# motorboard_2017.net
KiCad netlist of a schematic drawn in EAGLE
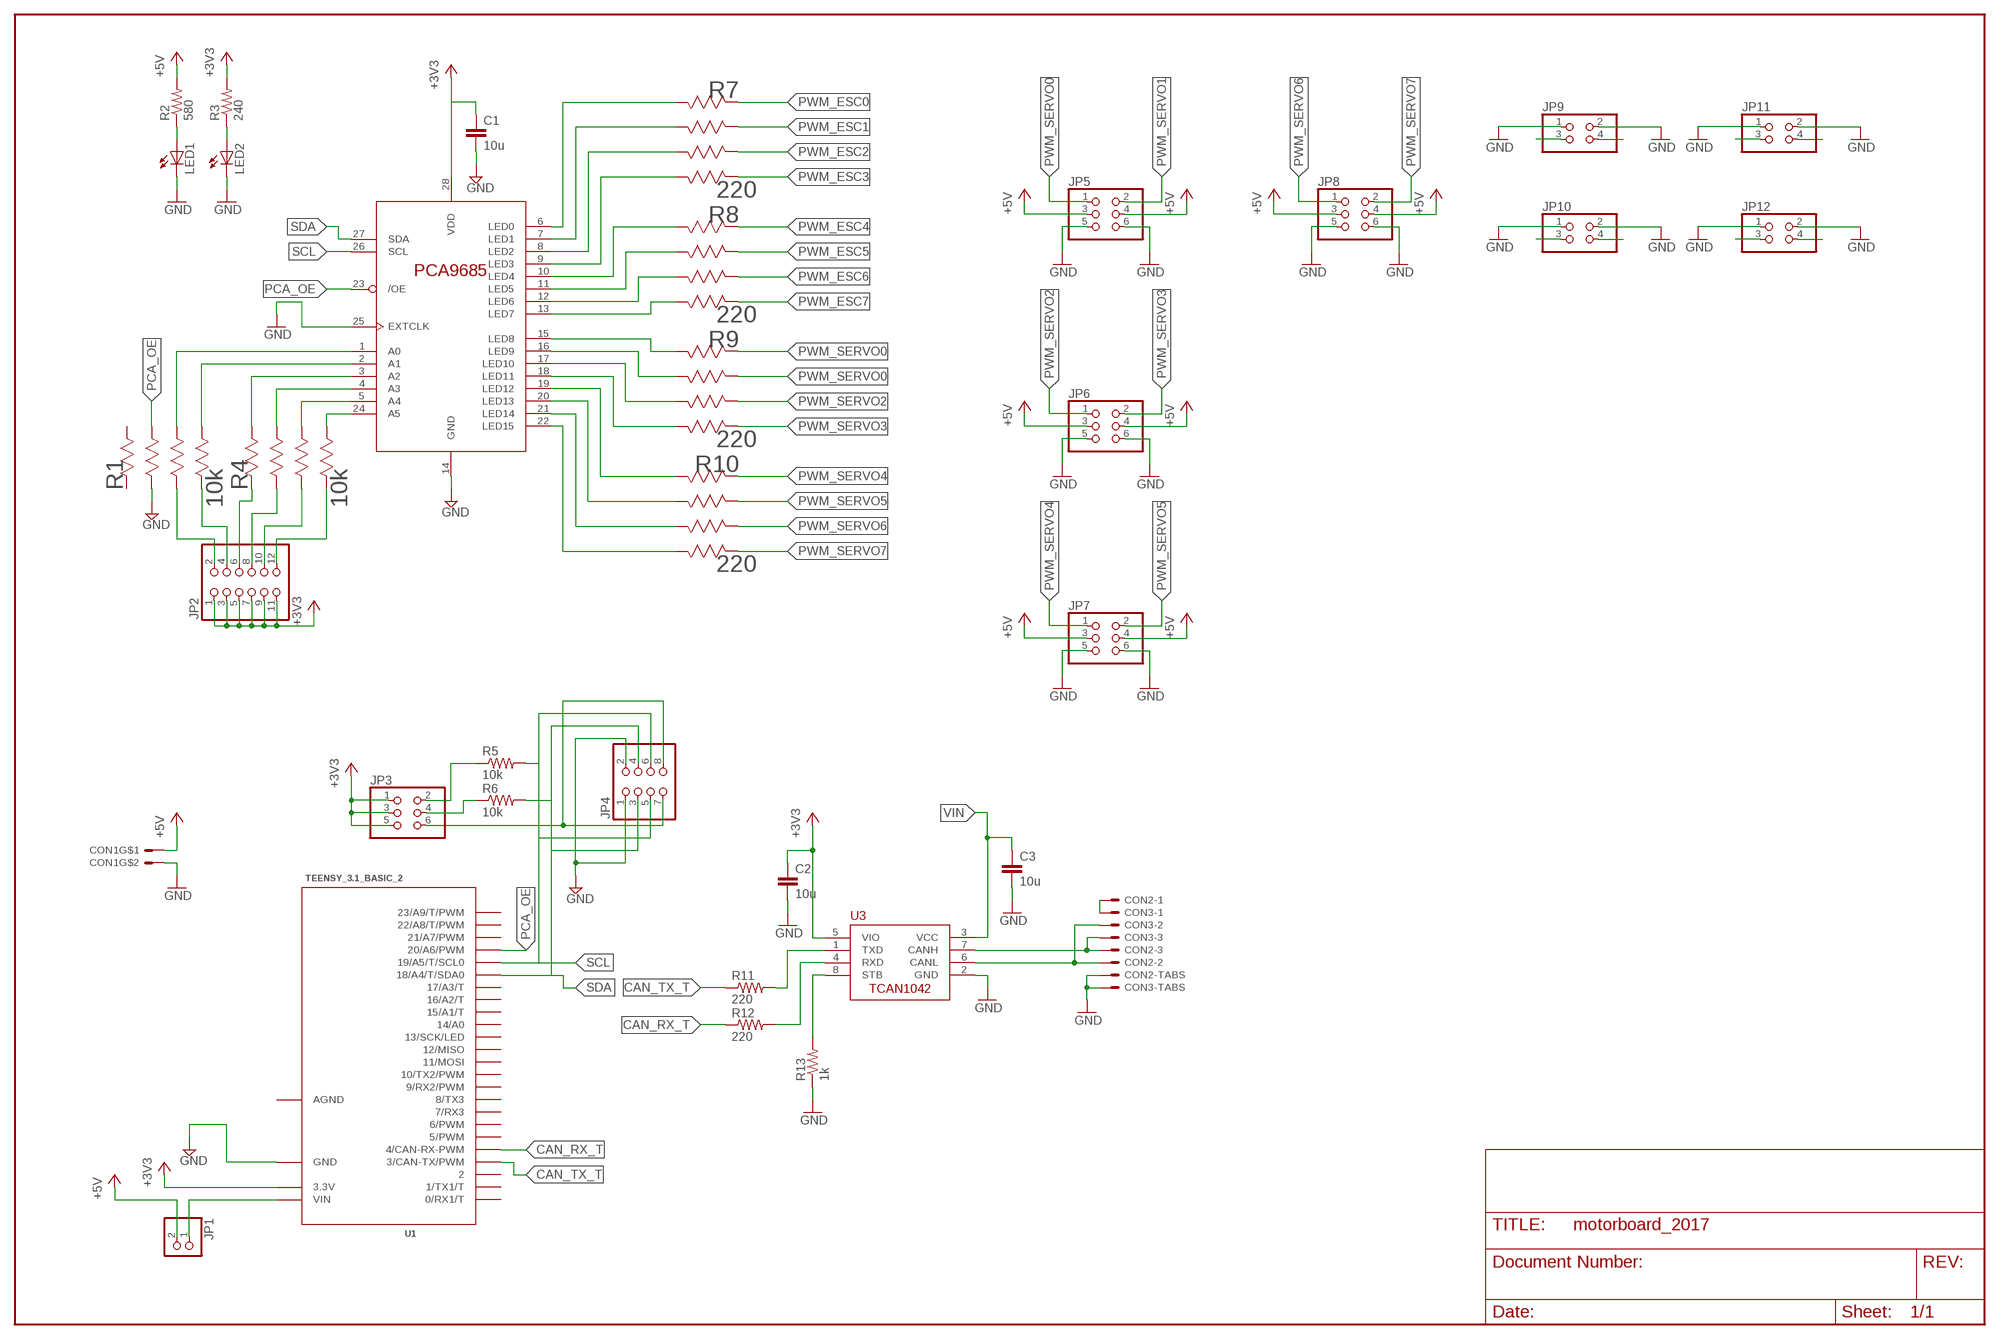
[diagram p0: schematic, sheet 1]

(export (version "E")
  (design (tool "Eeschema 10.0.6"))
  (components
    (comp (ref "C1")
      (value "10u")
      (footprint "eagle-import:C0805")
      (libsource (lib "eagle-import") (part "C-EUC0805"))
    )
    (comp (ref "C2")
      (value "10u")
      (footprint "eagle-import:C0805")
      (libsource (lib "eagle-import") (part "C-EUC0805"))
    )
    (comp (ref "C3")
      (value "10u")
      (footprint "eagle-import:C0805")
      (libsource (lib "eagle-import") (part "C-EUC0805"))
    )
    (comp (ref "CON1")
      (value "MOLEX_5566-2")
      (footprint "eagle-import:5566-2")
      (libsource (lib "eagle-import") (part "MOLEX_5566-2"))
    )
    (comp (ref "CON2")
      (value "SM03B-GHS-TB")
      (footprint "eagle-import:SM03B-GHS-TB")
      (libsource (lib "eagle-import") (part "SM03B-GHS-TB"))
    )
    (comp (ref "CON3")
      (value "SM03B-GHS-TB")
      (footprint "eagle-import:SM03B-GHS-TB")
      (libsource (lib "eagle-import") (part "SM03B-GHS-TB"))
    )
    (comp (ref "JP1")
      (value "PINHD-1X2")
      (footprint "eagle-import:1X02")
      (libsource (lib "eagle-import") (part "PINHD-1X2"))
    )
    (comp (ref "JP2")
      (value "PINHD-2X6")
      (footprint "eagle-import:2X06")
      (libsource (lib "eagle-import") (part "PINHD-2X6"))
    )
    (comp (ref "JP3")
      (value "PINHD-2X3")
      (footprint "eagle-import:2X03")
      (libsource (lib "eagle-import") (part "PINHD-2X3"))
    )
    (comp (ref "JP4")
      (value "PINHD-2X4")
      (footprint "eagle-import:2X04")
      (libsource (lib "eagle-import") (part "PINHD-2X4"))
    )
    (comp (ref "JP5")
      (value "PINHD-2X3")
      (footprint "eagle-import:2X03")
      (libsource (lib "eagle-import") (part "PINHD-2X3"))
    )
    (comp (ref "JP6")
      (value "PINHD-2X3")
      (footprint "eagle-import:2X03")
      (libsource (lib "eagle-import") (part "PINHD-2X3"))
    )
    (comp (ref "JP7")
      (value "PINHD-2X3")
      (footprint "eagle-import:2X03")
      (libsource (lib "eagle-import") (part "PINHD-2X3"))
    )
    (comp (ref "JP8")
      (value "PINHD-2X3")
      (footprint "eagle-import:2X03")
      (libsource (lib "eagle-import") (part "PINHD-2X3"))
    )
    (comp (ref "JP9")
      (value "PINHD-2X2")
      (footprint "eagle-import:2X02")
      (libsource (lib "eagle-import") (part "PINHD-2X2"))
    )
    (comp (ref "JP10")
      (value "PINHD-2X2")
      (footprint "eagle-import:2X02")
      (libsource (lib "eagle-import") (part "PINHD-2X2"))
    )
    (comp (ref "JP11")
      (value "PINHD-2X2")
      (footprint "eagle-import:2X02")
      (libsource (lib "eagle-import") (part "PINHD-2X2"))
    )
    (comp (ref "JP12")
      (value "PINHD-2X2")
      (footprint "eagle-import:2X02")
      (libsource (lib "eagle-import") (part "PINHD-2X2"))
    )
    (comp (ref "LED1")
      (value "LEDCHIPLED_1206")
      (footprint "eagle-import:CHIPLED_1206")
      (libsource (lib "eagle-import") (part "LEDCHIPLED_1206"))
    )
    (comp (ref "LED2")
      (value "LEDCHIPLED_1206")
      (footprint "eagle-import:CHIPLED_1206")
      (libsource (lib "eagle-import") (part "LEDCHIPLED_1206"))
    )
    (comp (ref "R1")
      (value "10k")
      (footprint "eagle-import:EXBV8V-M")
      (fields (field (name "MANUFACTURER_PART_NUMBER") "EXBV8V221JV"))
      (libsource (lib "eagle-import") (part "EXB-V8V221JVEXBV8V-M"))
    )
    (comp (ref "R2")
      (value "580")
      (footprint "eagle-import:R1206")
      (libsource (lib "eagle-import") (part "R-US_R1206"))
    )
    (comp (ref "R3")
      (value "240")
      (footprint "eagle-import:R1206")
      (libsource (lib "eagle-import") (part "R-US_R1206"))
    )
    (comp (ref "R4")
      (value "10k")
      (footprint "eagle-import:EXBV8V-M")
      (fields (field (name "MANUFACTURER_PART_NUMBER") "EXBV8V221JV"))
      (libsource (lib "eagle-import") (part "EXB-V8V221JVEXBV8V-M"))
    )
    (comp (ref "R5")
      (value "10k")
      (footprint "eagle-import:R1206")
      (libsource (lib "eagle-import") (part "R-US_R1206"))
    )
    (comp (ref "R6")
      (value "10k")
      (footprint "eagle-import:R1206")
      (libsource (lib "eagle-import") (part "R-US_R1206"))
    )
    (comp (ref "R7")
      (value "220")
      (footprint "eagle-import:EXBV8V-M")
      (fields (field (name "MANUFACTURER_PART_NUMBER") "EXBV8V221JV"))
      (libsource (lib "eagle-import") (part "EXB-V8V221JVEXBV8V-M"))
    )
    (comp (ref "R8")
      (value "220")
      (footprint "eagle-import:EXBV8V-M")
      (fields (field (name "MANUFACTURER_PART_NUMBER") "EXBV8V221JV"))
      (libsource (lib "eagle-import") (part "EXB-V8V221JVEXBV8V-M"))
    )
    (comp (ref "R9")
      (value "220")
      (footprint "eagle-import:EXBV8V-M")
      (fields (field (name "MANUFACTURER_PART_NUMBER") "EXBV8V221JV"))
      (libsource (lib "eagle-import") (part "EXB-V8V221JVEXBV8V-M"))
    )
    (comp (ref "R10")
      (value "220")
      (footprint "eagle-import:EXBV8V-M")
      (fields (field (name "MANUFACTURER_PART_NUMBER") "EXBV8V221JV"))
      (libsource (lib "eagle-import") (part "EXB-V8V221JVEXBV8V-M"))
    )
    (comp (ref "R11")
      (value "220")
      (footprint "eagle-import:R0805")
      (libsource (lib "eagle-import") (part "R-US_R0805"))
    )
    (comp (ref "R12")
      (value "220")
      (footprint "eagle-import:R0805")
      (libsource (lib "eagle-import") (part "R-US_R0805"))
    )
    (comp (ref "R13")
      (value "1k")
      (footprint "eagle-import:R0805")
      (libsource (lib "eagle-import") (part "R-US_R0805"))
    )
    (comp (ref "U1")
      (value "TEENSY_3.1_BASIC_2")
      (footprint "eagle-import:TEENSY_3.1_BASIC_2")
      (libsource (lib "eagle-import") (part "TEENSY_3.1_BASIC_2"))
    )
    (comp (ref "U2")
      (value "PCA9685PW")
      (footprint "eagle-import:TSSOP28")
      (libsource (lib "eagle-import") (part "PCA9685PW"))
    )
    (comp (ref "U3")
      (value "TCAN1042HVDR")
      (footprint "eagle-import:SO-8")
      (libsource (lib "eagle-import") (part "TCAN1042HVDR"))
    )
  )
  (nets
    (net (code "1") (name "+3V3") (class "Default")
      (node (ref "C1") (pin "1") (pinfunction "1_1") (pintype "passive"))
      (node (ref "C2") (pin "1") (pinfunction "1_1") (pintype "passive"))
      (node (ref "JP2") (pin "1") (pinfunction "1_1") (pintype "passive"))
      (node (ref "JP2") (pin "11") (pinfunction "11_11") (pintype "passive"))
      (node (ref "JP2") (pin "3") (pinfunction "3_3") (pintype "passive"))
      (node (ref "JP2") (pin "5") (pinfunction "5_5") (pintype "passive"))
      (node (ref "JP2") (pin "7") (pinfunction "7_7") (pintype "passive"))
      (node (ref "JP2") (pin "9") (pinfunction "9_9") (pintype "passive"))
      (node (ref "JP3") (pin "1") (pinfunction "1_1") (pintype "passive"))
      (node (ref "JP3") (pin "3") (pinfunction "3_3") (pintype "passive"))
      (node (ref "JP3") (pin "5") (pinfunction "5_5") (pintype "passive"))
      (node (ref "R3") (pin "2") (pinfunction "2_2") (pintype "passive"))
      (node (ref "U1") (pin "3.3V") (pinfunction "3.3V_3.3V") (pintype "power_in"))
      (node (ref "U2") (pin "28") (pinfunction "VDD_28") (pintype "power_in"))
      (node (ref "U3") (pin "5") (pinfunction "VIO_5") (pintype "bidirectional"))
    )
    (net (code "2") (name "+5V") (class "Default")
      (node (ref "CON1") (pin "1") (pinfunction "S_1") (pintype "passive"))
      (node (ref "JP1") (pin "2") (pinfunction "2_2") (pintype "passive"))
      (node (ref "JP5") (pin "3") (pinfunction "3_3") (pintype "passive"))
      (node (ref "JP5") (pin "4") (pinfunction "4_4") (pintype "passive"))
      (node (ref "JP6") (pin "3") (pinfunction "3_3") (pintype "passive"))
      (node (ref "JP6") (pin "4") (pinfunction "4_4") (pintype "passive"))
      (node (ref "JP7") (pin "3") (pinfunction "3_3") (pintype "passive"))
      (node (ref "JP7") (pin "4") (pinfunction "4_4") (pintype "passive"))
      (node (ref "JP8") (pin "3") (pinfunction "3_3") (pintype "passive"))
      (node (ref "JP8") (pin "4") (pinfunction "4_4") (pintype "passive"))
      (node (ref "R2") (pin "2") (pinfunction "2_2") (pintype "passive"))
    )
    (net (code "3") (name "/AGND") (class "Default")
      (node (ref "U1") (pin "AGND") (pinfunction "AGND_AGND") (pintype "power_in"))
    )
    (net (code "4") (name "CAN_RX_T") (class "Default")
      (node (ref "R12") (pin "1") (pinfunction "1_1") (pintype "passive"))
      (node (ref "U1") (pin "4") (pinfunction "4/CAN-RX-PWM_4") (pintype "bidirectional"))
    )
    (net (code "5") (name "CAN_TX_T") (class "Default")
      (node (ref "R11") (pin "1") (pinfunction "1_1") (pintype "passive"))
      (node (ref "U1") (pin "3") (pinfunction "3/CAN-TX/PWM_3") (pintype "bidirectional"))
    )
    (net (code "6") (name "GND") (class "Default")
      (node (ref "C1") (pin "2") (pinfunction "2_2") (pintype "passive"))
      (node (ref "C2") (pin "2") (pinfunction "2_2") (pintype "passive"))
      (node (ref "C3") (pin "2") (pinfunction "2_2") (pintype "passive"))
      (node (ref "CON1") (pin "2") (pinfunction "S_2") (pintype "passive"))
      (node (ref "CON2") (pin "P$4") (pinfunction "S_P$4") (pintype "passive"))
      (node (ref "CON2") (pin "P$5") (pinfunction "S_P$5") (pintype "passive"))
      (node (ref "CON3") (pin "P$4") (pinfunction "S_P$4") (pintype "passive"))
      (node (ref "CON3") (pin "P$5") (pinfunction "S_P$5") (pintype "passive"))
      (node (ref "JP10") (pin "1") (pinfunction "1_1") (pintype "passive"))
      (node (ref "JP10") (pin "2") (pinfunction "2_2") (pintype "passive"))
      (node (ref "JP11") (pin "1") (pinfunction "1_1") (pintype "passive"))
      (node (ref "JP11") (pin "2") (pinfunction "2_2") (pintype "passive"))
      (node (ref "JP12") (pin "1") (pinfunction "1_1") (pintype "passive"))
      (node (ref "JP12") (pin "2") (pinfunction "2_2") (pintype "passive"))
      (node (ref "JP4") (pin "1") (pinfunction "1_1") (pintype "passive"))
      (node (ref "JP4") (pin "2") (pinfunction "2_2") (pintype "passive"))
      (node (ref "JP5") (pin "5") (pinfunction "5_5") (pintype "passive"))
      (node (ref "JP5") (pin "6") (pinfunction "6_6") (pintype "passive"))
      (node (ref "JP6") (pin "5") (pinfunction "5_5") (pintype "passive"))
      (node (ref "JP6") (pin "6") (pinfunction "6_6") (pintype "passive"))
      (node (ref "JP7") (pin "5") (pinfunction "5_5") (pintype "passive"))
      (node (ref "JP7") (pin "6") (pinfunction "6_6") (pintype "passive"))
      (node (ref "JP8") (pin "5") (pinfunction "5_5") (pintype "passive"))
      (node (ref "JP8") (pin "6") (pinfunction "6_6") (pintype "passive"))
      (node (ref "JP9") (pin "1") (pinfunction "1_1") (pintype "passive"))
      (node (ref "JP9") (pin "2") (pinfunction "2_2") (pintype "passive"))
      (node (ref "LED1") (pin "C") (pinfunction "C_C") (pintype "passive"))
      (node (ref "LED2") (pin "C") (pinfunction "C_C") (pintype "passive"))
      (node (ref "R1") (pin "2") (pinfunction "23_2") (pintype "passive"))
      (node (ref "R13") (pin "1") (pinfunction "1_1") (pintype "passive"))
      (node (ref "U1") (pin "GND") (pinfunction "GND_GND") (pintype "power_in"))
      (node (ref "U2") (pin "14") (pinfunction "GND_14") (pintype "power_in"))
      (node (ref "U2") (pin "25") (pinfunction "EXTCLK_25") (pintype "input"))
      (node (ref "U3") (pin "2") (pinfunction "GND_2") (pintype "bidirectional"))
    )
    (net (code "7") (name "Net-(CON2A-S)") (class "Default")
      (node (ref "CON2") (pin "P$1") (pinfunction "S_P$1") (pintype "passive"))
      (node (ref "CON3") (pin "P$1") (pinfunction "S_P$1") (pintype "passive"))
    )
    (net (code "8") (name "Net-(CON2B-S)") (class "Default")
      (node (ref "CON2") (pin "P$2") (pinfunction "S_P$2") (pintype "passive"))
      (node (ref "CON3") (pin "P$2") (pinfunction "S_P$2") (pintype "passive"))
      (node (ref "U3") (pin "6") (pinfunction "CANL_6") (pintype "bidirectional"))
    )
    (net (code "9") (name "Net-(CON2C-S)") (class "Default")
      (node (ref "CON2") (pin "P$3") (pinfunction "S_P$3") (pintype "passive"))
      (node (ref "CON3") (pin "P$3") (pinfunction "S_P$3") (pintype "passive"))
      (node (ref "U3") (pin "7") (pinfunction "CANH_7") (pintype "bidirectional"))
    )
    (net (code "10") (name "Net-(JP3-Pad2)") (class "Default")
      (node (ref "JP3") (pin "2") (pinfunction "2_2") (pintype "passive"))
      (node (ref "R5") (pin "1") (pinfunction "1_1") (pintype "passive"))
    )
    (net (code "11") (name "Net-(JP3-Pad4)") (class "Default")
      (node (ref "JP3") (pin "4") (pinfunction "4_4") (pintype "passive"))
      (node (ref "R6") (pin "1") (pinfunction "1_1") (pintype "passive"))
    )
    (net (code "12") (name "Net-(JP3-Pad6)") (class "Default")
      (node (ref "JP3") (pin "6") (pinfunction "6_6") (pintype "passive"))
      (node (ref "JP4") (pin "7") (pinfunction "7_7") (pintype "passive"))
      (node (ref "JP4") (pin "8") (pinfunction "8_8") (pintype "passive"))
    )
    (net (code "13") (name "Net-(LED1-PadA)") (class "Default")
      (node (ref "LED1") (pin "A") (pinfunction "A_A") (pintype "passive"))
      (node (ref "R2") (pin "1") (pinfunction "1_1") (pintype "passive"))
    )
    (net (code "14") (name "Net-(LED2-PadA)") (class "Default")
      (node (ref "LED2") (pin "A") (pinfunction "A_A") (pintype "passive"))
      (node (ref "R3") (pin "1") (pinfunction "1_1") (pintype "passive"))
    )
    (net (code "15") (name "Net-(R1-35)") (class "Default")
      (node (ref "JP2") (pin "2") (pinfunction "2_2") (pintype "passive"))
      (node (ref "R1") (pin "3") (pinfunction "35_3") (pintype "passive"))
    )
    (net (code "16") (name "Net-(R1-47)") (class "Default")
      (node (ref "JP2") (pin "4") (pinfunction "4_4") (pintype "passive"))
      (node (ref "R1") (pin "4") (pinfunction "47_4") (pintype "passive"))
    )
    (net (code "17") (name "Net-(R1-58)") (class "Default")
      (node (ref "R1") (pin "5") (pinfunction "58_5") (pintype "passive"))
      (node (ref "U2") (pin "2") (pinfunction "A1_2") (pintype "bidirectional"))
    )
    (net (code "18") (name "Net-(R1-66)") (class "Default")
      (node (ref "R1") (pin "6") (pinfunction "66_6") (pintype "passive"))
      (node (ref "U2") (pin "1") (pinfunction "A0_1") (pintype "bidirectional"))
    )
    (net (code "19") (name "Net-(R4-11)") (class "Default")
      (node (ref "JP2") (pin "6") (pinfunction "6_6") (pintype "passive"))
      (node (ref "R4") (pin "1") (pinfunction "11_1") (pintype "passive"))
    )
    (net (code "20") (name "Net-(R4-23)") (class "Default")
      (node (ref "JP2") (pin "8") (pinfunction "8_8") (pintype "passive"))
      (node (ref "R4") (pin "2") (pinfunction "23_2") (pintype "passive"))
    )
    (net (code "21") (name "Net-(R4-35)") (class "Default")
      (node (ref "JP2") (pin "10") (pinfunction "10_10") (pintype "passive"))
      (node (ref "R4") (pin "3") (pinfunction "35_3") (pintype "passive"))
    )
    (net (code "22") (name "Net-(R4-47)") (class "Default")
      (node (ref "JP2") (pin "12") (pinfunction "12_12") (pintype "passive"))
      (node (ref "R4") (pin "4") (pinfunction "47_4") (pintype "passive"))
    )
    (net (code "23") (name "Net-(R4-58)") (class "Default")
      (node (ref "R4") (pin "5") (pinfunction "58_5") (pintype "passive"))
      (node (ref "U2") (pin "24") (pinfunction "A5_24") (pintype "bidirectional"))
    )
    (net (code "24") (name "Net-(R4-66)") (class "Default")
      (node (ref "R4") (pin "6") (pinfunction "66_6") (pintype "passive"))
      (node (ref "U2") (pin "5") (pinfunction "A4_5") (pintype "bidirectional"))
    )
    (net (code "25") (name "Net-(R4-74)") (class "Default")
      (node (ref "R4") (pin "7") (pinfunction "74_7") (pintype "passive"))
      (node (ref "U2") (pin "4") (pinfunction "A3_4") (pintype "bidirectional"))
    )
    (net (code "26") (name "Net-(R4-82)") (class "Default")
      (node (ref "R4") (pin "8") (pinfunction "82_8") (pintype "passive"))
      (node (ref "U2") (pin "3") (pinfunction "A2_3") (pintype "bidirectional"))
    )
    (net (code "27") (name "Net-(R7-58)") (class "Default")
      (node (ref "R7") (pin "5") (pinfunction "58_5") (pintype "passive"))
      (node (ref "U2") (pin "9") (pinfunction "LED3_9") (pintype "bidirectional"))
    )
    (net (code "28") (name "Net-(R7-66)") (class "Default")
      (node (ref "R7") (pin "6") (pinfunction "66_6") (pintype "passive"))
      (node (ref "U2") (pin "8") (pinfunction "LED2_8") (pintype "bidirectional"))
    )
    (net (code "29") (name "Net-(R7-74)") (class "Default")
      (node (ref "R7") (pin "7") (pinfunction "74_7") (pintype "passive"))
      (node (ref "U2") (pin "7") (pinfunction "LED1_7") (pintype "bidirectional"))
    )
    (net (code "30") (name "Net-(R7-82)") (class "Default")
      (node (ref "R7") (pin "8") (pinfunction "82_8") (pintype "passive"))
      (node (ref "U2") (pin "6") (pinfunction "LED0_6") (pintype "bidirectional"))
    )
    (net (code "31") (name "Net-(R8-58)") (class "Default")
      (node (ref "R8") (pin "5") (pinfunction "58_5") (pintype "passive"))
      (node (ref "U2") (pin "13") (pinfunction "LED7_13") (pintype "bidirectional"))
    )
    (net (code "32") (name "Net-(R8-66)") (class "Default")
      (node (ref "R8") (pin "6") (pinfunction "66_6") (pintype "passive"))
      (node (ref "U2") (pin "12") (pinfunction "LED6_12") (pintype "bidirectional"))
    )
    (net (code "33") (name "Net-(R8-74)") (class "Default")
      (node (ref "R8") (pin "7") (pinfunction "74_7") (pintype "passive"))
      (node (ref "U2") (pin "11") (pinfunction "LED5_11") (pintype "bidirectional"))
    )
    (net (code "34") (name "Net-(R8-82)") (class "Default")
      (node (ref "R8") (pin "8") (pinfunction "82_8") (pintype "passive"))
      (node (ref "U2") (pin "10") (pinfunction "LED4_10") (pintype "bidirectional"))
    )
    (net (code "35") (name "Net-(R9-58)") (class "Default")
      (node (ref "R9") (pin "5") (pinfunction "58_5") (pintype "passive"))
      (node (ref "U2") (pin "18") (pinfunction "LED11_18") (pintype "bidirectional"))
    )
    (net (code "36") (name "Net-(R9-66)") (class "Default")
      (node (ref "R9") (pin "6") (pinfunction "66_6") (pintype "passive"))
      (node (ref "U2") (pin "17") (pinfunction "LED10_17") (pintype "bidirectional"))
    )
    (net (code "37") (name "Net-(R9-74)") (class "Default")
      (node (ref "R9") (pin "7") (pinfunction "74_7") (pintype "passive"))
      (node (ref "U2") (pin "16") (pinfunction "LED9_16") (pintype "bidirectional"))
    )
    (net (code "38") (name "Net-(R9-82)") (class "Default")
      (node (ref "R9") (pin "8") (pinfunction "82_8") (pintype "passive"))
      (node (ref "U2") (pin "15") (pinfunction "LED8_15") (pintype "bidirectional"))
    )
    (net (code "39") (name "Net-(R10-58)") (class "Default")
      (node (ref "R10") (pin "5") (pinfunction "58_5") (pintype "passive"))
      (node (ref "U2") (pin "22") (pinfunction "LED15_22") (pintype "bidirectional"))
    )
    (net (code "40") (name "Net-(R10-66)") (class "Default")
      (node (ref "R10") (pin "6") (pinfunction "66_6") (pintype "passive"))
      (node (ref "U2") (pin "21") (pinfunction "LED14_21") (pintype "bidirectional"))
    )
    (net (code "41") (name "Net-(R10-74)") (class "Default")
      (node (ref "R10") (pin "7") (pinfunction "74_7") (pintype "passive"))
      (node (ref "U2") (pin "20") (pinfunction "LED13_20") (pintype "bidirectional"))
    )
    (net (code "42") (name "Net-(R10-82)") (class "Default")
      (node (ref "R10") (pin "8") (pinfunction "82_8") (pintype "passive"))
      (node (ref "U2") (pin "19") (pinfunction "LED12_19") (pintype "bidirectional"))
    )
    (net (code "43") (name "Net-(U3-RXD)") (class "Default")
      (node (ref "R12") (pin "2") (pinfunction "2_2") (pintype "passive"))
      (node (ref "U3") (pin "4") (pinfunction "RXD_4") (pintype "bidirectional"))
    )
    (net (code "44") (name "Net-(U3-STB)") (class "Default")
      (node (ref "R13") (pin "2") (pinfunction "2_2") (pintype "passive"))
      (node (ref "U3") (pin "8") (pinfunction "STB_8") (pintype "bidirectional"))
    )
    (net (code "45") (name "Net-(U3-TXD)") (class "Default")
      (node (ref "R11") (pin "2") (pinfunction "2_2") (pintype "passive"))
      (node (ref "U3") (pin "1") (pinfunction "TXD_1") (pintype "bidirectional"))
    )
    (net (code "46") (name "PCA_OE") (class "Default")
      (node (ref "R1") (pin "7") (pinfunction "74_7") (pintype "passive"))
      (node (ref "U1") (pin "20/A6") (pinfunction "20/A6/PWM_20/A6") (pintype "bidirectional"))
      (node (ref "U2") (pin "23") (pinfunction "/OE_23") (pintype "bidirectional"))
    )
    (net (code "47") (name "PWM_ESC0") (class "Default")
      (node (ref "JP12") (pin "4") (pinfunction "4_4") (pintype "passive"))
      (node (ref "R7") (pin "1") (pinfunction "11_1") (pintype "passive"))
    )
    (net (code "48") (name "PWM_ESC1") (class "Default")
      (node (ref "JP12") (pin "3") (pinfunction "3_3") (pintype "passive"))
      (node (ref "R7") (pin "2") (pinfunction "23_2") (pintype "passive"))
    )
    (net (code "49") (name "PWM_ESC2") (class "Default")
      (node (ref "JP9") (pin "4") (pinfunction "4_4") (pintype "passive"))
      (node (ref "R7") (pin "3") (pinfunction "35_3") (pintype "passive"))
    )
    (net (code "50") (name "PWM_ESC3") (class "Default")
      (node (ref "JP9") (pin "3") (pinfunction "3_3") (pintype "passive"))
      (node (ref "R7") (pin "4") (pinfunction "47_4") (pintype "passive"))
    )
    (net (code "51") (name "PWM_ESC4") (class "Default")
      (node (ref "JP11") (pin "4") (pinfunction "4_4") (pintype "passive"))
      (node (ref "R8") (pin "1") (pinfunction "11_1") (pintype "passive"))
    )
    (net (code "52") (name "PWM_ESC5") (class "Default")
      (node (ref "JP11") (pin "3") (pinfunction "3_3") (pintype "passive"))
      (node (ref "R8") (pin "2") (pinfunction "23_2") (pintype "passive"))
    )
    (net (code "53") (name "PWM_ESC6") (class "Default")
      (node (ref "JP10") (pin "4") (pinfunction "4_4") (pintype "passive"))
      (node (ref "R8") (pin "3") (pinfunction "35_3") (pintype "passive"))
    )
    (net (code "54") (name "PWM_ESC7") (class "Default")
      (node (ref "JP10") (pin "3") (pinfunction "3_3") (pintype "passive"))
      (node (ref "R8") (pin "4") (pinfunction "47_4") (pintype "passive"))
    )
    (net (code "55") (name "PWM_SERVO0") (class "Default")
      (node (ref "JP5") (pin "1") (pinfunction "1_1") (pintype "passive"))
      (node (ref "R9") (pin "1") (pinfunction "11_1") (pintype "passive"))
    )
    (net (code "56") (name "PWM_SERVO1") (class "Default")
      (node (ref "JP5") (pin "2") (pinfunction "2_2") (pintype "passive"))
      (node (ref "R9") (pin "2") (pinfunction "23_2") (pintype "passive"))
    )
    (net (code "57") (name "PWM_SERVO2") (class "Default")
      (node (ref "JP6") (pin "1") (pinfunction "1_1") (pintype "passive"))
      (node (ref "R9") (pin "3") (pinfunction "35_3") (pintype "passive"))
    )
    (net (code "58") (name "PWM_SERVO3") (class "Default")
      (node (ref "JP6") (pin "2") (pinfunction "2_2") (pintype "passive"))
      (node (ref "R9") (pin "4") (pinfunction "47_4") (pintype "passive"))
    )
    (net (code "59") (name "PWM_SERVO4") (class "Default")
      (node (ref "JP7") (pin "1") (pinfunction "1_1") (pintype "passive"))
      (node (ref "R10") (pin "1") (pinfunction "11_1") (pintype "passive"))
    )
    (net (code "60") (name "PWM_SERVO5") (class "Default")
      (node (ref "JP7") (pin "2") (pinfunction "2_2") (pintype "passive"))
      (node (ref "R10") (pin "2") (pinfunction "23_2") (pintype "passive"))
    )
    (net (code "61") (name "PWM_SERVO6") (class "Default")
      (node (ref "JP8") (pin "1") (pinfunction "1_1") (pintype "passive"))
      (node (ref "R10") (pin "3") (pinfunction "35_3") (pintype "passive"))
    )
    (net (code "62") (name "PWM_SERVO7") (class "Default")
      (node (ref "JP8") (pin "2") (pinfunction "2_2") (pintype "passive"))
      (node (ref "R10") (pin "4") (pinfunction "47_4") (pintype "passive"))
    )
    (net (code "63") (name "SCL") (class "Default")
      (node (ref "JP4") (pin "5") (pinfunction "5_5") (pintype "passive"))
      (node (ref "JP4") (pin "6") (pinfunction "6_6") (pintype "passive"))
      (node (ref "R5") (pin "2") (pinfunction "2_2") (pintype "passive"))
      (node (ref "U1") (pin "19/A5") (pinfunction "19/A5/T/SCL0_19/A5") (pintype "bidirectional"))
      (node (ref "U2") (pin "26") (pinfunction "SCL_26") (pintype "bidirectional"))
    )
    (net (code "64") (name "SDA") (class "Default")
      (node (ref "JP4") (pin "3") (pinfunction "3_3") (pintype "passive"))
      (node (ref "JP4") (pin "4") (pinfunction "4_4") (pintype "passive"))
      (node (ref "R6") (pin "2") (pinfunction "2_2") (pintype "passive"))
      (node (ref "U1") (pin "18/A4") (pinfunction "18/A4/T/SDA0_18/A4") (pintype "bidirectional"))
      (node (ref "U2") (pin "27") (pinfunction "SDA_27") (pintype "bidirectional"))
    )
    (net (code "65") (name "VIN") (class "Default")
      (node (ref "C3") (pin "1") (pinfunction "1_1") (pintype "passive"))
      (node (ref "JP1") (pin "1") (pinfunction "1_1") (pintype "passive"))
      (node (ref "U1") (pin "VIN") (pinfunction "VIN_VIN") (pintype "power_in"))
      (node (ref "U3") (pin "3") (pinfunction "VCC_3") (pintype "bidirectional"))
    )
    (net (code "66") (name "unconnected-(R1-11-Pad1)") (class "Default")
      (node (ref "R1") (pin "1") (pinfunction "11_1") (pintype "passive"))
    )
    (net (code "67") (name "unconnected-(R1-82-Pad8)") (class "Default")
      (node (ref "R1") (pin "8") (pinfunction "82_8") (pintype "passive"))
    )
    (net (code "68") (name "unconnected-(U1-0{slash}RX1{slash}T-Pad0)") (class "Default")
      (node (ref "U1") (pin "0") (pinfunction "0/RX1/T_0") (pintype "bidirectional"))
    )
    (net (code "69") (name "unconnected-(U1-1{slash}TX1{slash}T-Pad1)") (class "Default")
      (node (ref "U1") (pin "1") (pinfunction "1/TX1/T_1") (pintype "bidirectional"))
    )
    (net (code "70") (name "unconnected-(U1-5{slash}PWM-Pad5)") (class "Default")
      (node (ref "U1") (pin "5") (pinfunction "5/PWM_5") (pintype "bidirectional"))
    )
    (net (code "71") (name "unconnected-(U1-6{slash}PWM-Pad6)") (class "Default")
      (node (ref "U1") (pin "6") (pinfunction "6/PWM_6") (pintype "bidirectional"))
    )
    (net (code "72") (name "unconnected-(U1-7{slash}RX3-Pad7)") (class "Default")
      (node (ref "U1") (pin "7") (pinfunction "7/RX3_7") (pintype "bidirectional"))
    )
    (net (code "73") (name "unconnected-(U1-8{slash}TX3-Pad8)") (class "Default")
      (node (ref "U1") (pin "8") (pinfunction "8/TX3_8") (pintype "bidirectional"))
    )
    (net (code "74") (name "unconnected-(U1-9{slash}RX2{slash}PWM-Pad9)") (class "Default")
      (node (ref "U1") (pin "9") (pinfunction "9/RX2/PWM_9") (pintype "bidirectional"))
    )
    (net (code "75") (name "unconnected-(U1-10{slash}TX2{slash}PWM-Pad10)") (class "Default")
      (node (ref "U1") (pin "10") (pinfunction "10/TX2/PWM_10") (pintype "bidirectional"))
    )
    (net (code "76") (name "unconnected-(U1-11{slash}MOSI-Pad11)") (class "Default")
      (node (ref "U1") (pin "11") (pinfunction "11/MOSI_11") (pintype "bidirectional"))
    )
    (net (code "77") (name "unconnected-(U1-12{slash}MISO-Pad12)") (class "Default")
      (node (ref "U1") (pin "12") (pinfunction "12/MISO_12") (pintype "bidirectional"))
    )
    (net (code "78") (name "unconnected-(U1-13{slash}SCK{slash}LED-Pad13)") (class "Default")
      (node (ref "U1") (pin "13") (pinfunction "13/SCK/LED_13") (pintype "bidirectional"))
    )
    (net (code "79") (name "unconnected-(U1-15{slash}A1{slash}T-Pad15{slash}A1)") (class "Default")
      (node (ref "U1") (pin "15/A1") (pinfunction "15/A1/T_15/A1") (pintype "bidirectional"))
    )
    (net (code "80") (name "unconnected-(U1-16{slash}A2{slash}T-Pad16{slash}A2)") (class "Default")
      (node (ref "U1") (pin "16/A2") (pinfunction "16/A2/T_16/A2") (pintype "bidirectional"))
    )
    (net (code "81") (name "unconnected-(U1-17{slash}A3{slash}T-Pad17{slash}A3)") (class "Default")
      (node (ref "U1") (pin "17/A3") (pinfunction "17/A3/T_17/A3") (pintype "bidirectional"))
    )
    (net (code "82") (name "unconnected-(U1-21{slash}A7{slash}PWM-Pad21{slash}A7)") (class "Default")
      (node (ref "U1") (pin "21/A7") (pinfunction "21/A7/PWM_21/A7") (pintype "bidirectional"))
    )
    (net (code "83") (name "unconnected-(U1-22{slash}A8{slash}T{slash}PWM-Pad22{slash}A8)") (class "Default")
      (node (ref "U1") (pin "22/A8") (pinfunction "22/A8/T/PWM_22/A8") (pintype "bidirectional"))
    )
    (net (code "84") (name "unconnected-(U1-23{slash}A9{slash}T{slash}PWM-Pad23{slash}A9)") (class "Default")
      (node (ref "U1") (pin "23/A9") (pinfunction "23/A9/T/PWM_23/A9") (pintype "bidirectional"))
    )
    (net (code "85") (name "unconnected-(U1-Pad2)") (class "Default")
      (node (ref "U1") (pin "2") (pinfunction "2_2") (pintype "bidirectional"))
    )
    (net (code "86") (name "unconnected-(U1-Pad14{slash}A0)") (class "Default")
      (node (ref "U1") (pin "14/A0") (pinfunction "14/A0_14/A0") (pintype "bidirectional"))
    )
  )
)
